# MINI_SAM_D51_016.net
KiCad netlist of a schematic drawn in EAGLE
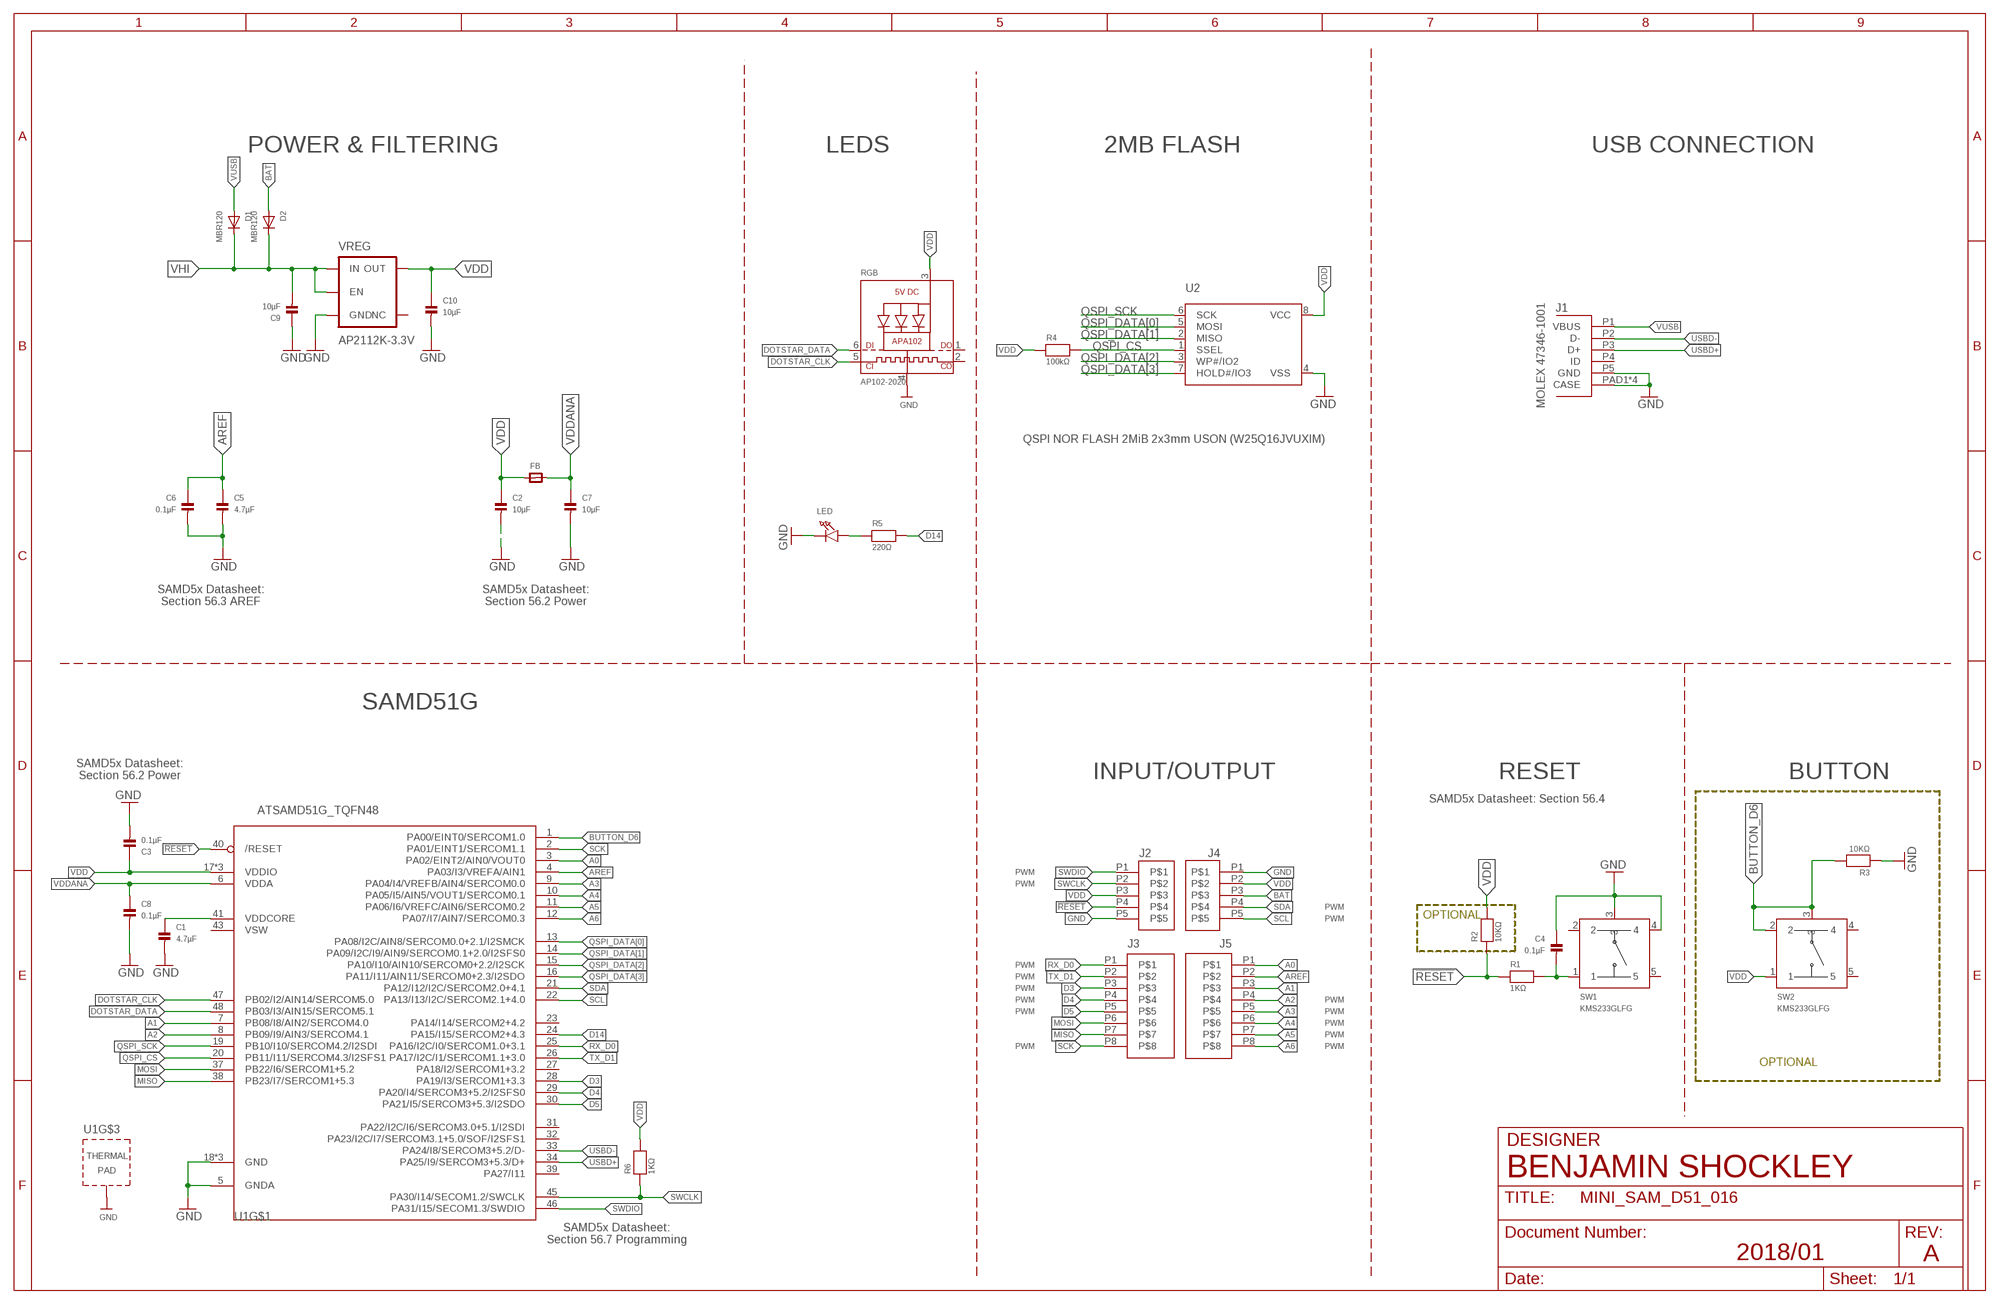
[diagram p0: schematic, sheet 1]

(export (version "E")
  (design (tool "Eeschema 10.0.6"))
  (components
    (comp (ref "C1")
      (value "4.7µF")
      (footprint "eagle-import:_0603MP")
      (libsource (lib "eagle-import") (part "CAP_CERAMIC_0603MP"))
    )
    (comp (ref "C2")
      (value "10µF")
      (footprint "eagle-import:_0603MP")
      (libsource (lib "eagle-import") (part "CAP_CERAMIC_0603MP"))
    )
    (comp (ref "C3")
      (value "0.1µF")
      (footprint "eagle-import:_0603MP")
      (libsource (lib "eagle-import") (part "CAP_CERAMIC_0603MP"))
    )
    (comp (ref "C4")
      (value "0.1µF")
      (footprint "eagle-import:_0603MP")
      (libsource (lib "eagle-import") (part "CAP_CERAMIC_0603MP"))
    )
    (comp (ref "C5")
      (value "4.7µF")
      (footprint "eagle-import:_0603MP")
      (libsource (lib "eagle-import") (part "CAP_CERAMIC_0603MP"))
    )
    (comp (ref "C6")
      (value "0.1µF")
      (footprint "eagle-import:_0603MP")
      (libsource (lib "eagle-import") (part "CAP_CERAMIC_0603MP"))
    )
    (comp (ref "C7")
      (value "10µF")
      (footprint "eagle-import:_0603MP")
      (libsource (lib "eagle-import") (part "CAP_CERAMIC_0603MP"))
    )
    (comp (ref "C8")
      (value "0.1µF")
      (footprint "eagle-import:_0603MP")
      (libsource (lib "eagle-import") (part "CAP_CERAMIC_0603MP"))
    )
    (comp (ref "C9")
      (value "10µF")
      (footprint "eagle-import:_0603MP")
      (libsource (lib "eagle-import") (part "CAP_CERAMIC_0603MP"))
    )
    (comp (ref "C10")
      (value "10µF")
      (footprint "eagle-import:_0603MP")
      (libsource (lib "eagle-import") (part "CAP_CERAMIC_0603MP"))
    )
    (comp (ref "D1")
      (value "MBR120")
      (footprint "eagle-import:SOD-123FL")
      (libsource (lib "eagle-import") (part "DIODE_SOD-123FL"))
    )
    (comp (ref "D2")
      (value "MBR120")
      (footprint "eagle-import:SOD-123FL")
      (libsource (lib "eagle-import") (part "DIODE_SOD-123FL"))
    )
    (comp (ref "FB")
      (value "Impedence: 50 ohm @ 20 MHz, 220 Ohm @ 100 MHz; low DC resistance")
      (footprint "eagle-import:_0603MP")
      (libsource (lib "eagle-import") (part "FERRITE_0603MP"))
    )
    (comp (ref "J1")
      (value "MOLEX_47346-100147346")
      (footprint "eagle-import:MOLEX_47346-1001")
      (libsource (lib "eagle-import") (part "MOLEX_47346-100147346"))
    )
    (comp (ref "J2")
      (value "1X5_HEADER_1.27MMCAST")
      (footprint "eagle-import:1X5_HEADER_1.27MM_CASTELLATED")
      (libsource (lib "eagle-import") (part "1X5_HEADER_1.27MMCAST"))
    )
    (comp (ref "J3")
      (value "1X8_HEADER_1.27MMCAST")
      (footprint "eagle-import:1X8_HEADER_1.27MM_CASTELLATED")
      (libsource (lib "eagle-import") (part "1X8_HEADER_1.27MMCAST"))
    )
    (comp (ref "J4")
      (value "1X5_HEADER_1.27MMCAST")
      (footprint "eagle-import:1X5_HEADER_1.27MM_CASTELLATED")
      (libsource (lib "eagle-import") (part "1X5_HEADER_1.27MMCAST"))
    )
    (comp (ref "J5")
      (value "1X8_HEADER_1.27MMCAST")
      (footprint "eagle-import:1X8_HEADER_1.27MM_CASTELLATED")
      (libsource (lib "eagle-import") (part "1X8_HEADER_1.27MMCAST"))
    )
    (comp (ref "LED")
      (value "Easily mounted up-sdie down.")
      (footprint "eagle-import:CHIPLED_0805_NOOUTLINE")
      (libsource (lib "eagle-import") (part "LED0805_NOOUTLINE"))
    )
    (comp (ref "R1")
      (value "1KΩ")
      (footprint "eagle-import:_0603MP")
      (libsource (lib "eagle-import") (part "RESISTOR_0603MP"))
    )
    (comp (ref "R2")
      (value "10KΩ")
      (footprint "eagle-import:_0603MP")
      (libsource (lib "eagle-import") (part "RESISTOR_0603MP"))
    )
    (comp (ref "R3")
      (value "10KΩ")
      (footprint "eagle-import:_0603MP")
      (libsource (lib "eagle-import") (part "RESISTOR_0603MP"))
    )
    (comp (ref "R4")
      (value "100kΩ")
      (footprint "eagle-import:_0603MP")
      (libsource (lib "eagle-import") (part "RESISTOR_0603MP"))
    )
    (comp (ref "R5")
      (value "220Ω")
      (footprint "eagle-import:_0603MP")
      (libsource (lib "eagle-import") (part "RESISTOR_0603MP"))
    )
    (comp (ref "R6")
      (value "1KΩ")
      (footprint "eagle-import:_0603MP")
      (libsource (lib "eagle-import") (part "RESISTOR_0603MP"))
    )
    (comp (ref "RGB")
      (value "AP102-2020")
      (footprint "eagle-import:APA102_2020")
      (libsource (lib "eagle-import") (part "APA1022020"))
    )
    (comp (ref "SW1")
      (value "KMS233GLFG")
      (footprint "eagle-import:KMS_SWITCH")
      (libsource (lib "eagle-import") (part "KMS_SWITCHKMS"))
    )
    (comp (ref "SW2")
      (value "KMS233GLFG")
      (footprint "eagle-import:KMS_SWITCH")
      (libsource (lib "eagle-import") (part "KMS_SWITCHKMS"))
    )
    (comp (ref "U1")
      (value "ATSAMD51G_TQFN48")
      (footprint "eagle-import:TQFN48_7MM")
      (libsource (lib "eagle-import") (part "ATSAMD51G_TQFN48"))
    )
    (comp (ref "U2")
      (value "QSPI NOR FLASH 2MiB 2x3mm USON (W25Q16JVUXIM)")
      (footprint "eagle-import:USON8")
      (libsource (lib "eagle-import") (part "SPIFLASH_8PINUX"))
    )
    (comp (ref "VREG")
      (value "AP2112K-3.3V")
      (footprint "eagle-import:SOT23-5")
      (libsource (lib "eagle-import") (part "V_REG_AP2112K-3.3V"))
    )
  )
  (nets
    (net (code "1") (name "/VSW") (class "Default")
      (node (ref "U1") (pin "43") (pinfunction "VSW_43") (pintype "power_in"))
    )
    (net (code "2") (name "/~{RESET}") (class "Default")
      (node (ref "J2") (pin "P4") (pinfunction "P$4_P4") (pintype "bidirectional"))
      (node (ref "R1") (pin "1") (pinfunction "1_1") (pintype "passive"))
      (node (ref "R2") (pin "1") (pinfunction "1_1") (pintype "passive"))
      (node (ref "U1") (pin "40") (pinfunction "/RESET_40") (pintype "bidirectional"))
    )
    (net (code "3") (name "A0") (class "Default")
      (node (ref "J5") (pin "P1") (pinfunction "P$1_P1") (pintype "bidirectional"))
      (node (ref "U1") (pin "3") (pinfunction "PA02/EINT2/AIN0/VOUT0_3") (pintype "bidirectional"))
    )
    (net (code "4") (name "A1") (class "Default")
      (node (ref "J5") (pin "P3") (pinfunction "P$3_P3") (pintype "bidirectional"))
      (node (ref "U1") (pin "7") (pinfunction "PB08/I8/AIN2/SERCOM4.0_7") (pintype "bidirectional"))
    )
    (net (code "5") (name "A2") (class "Default")
      (node (ref "J5") (pin "P4") (pinfunction "P$4_P4") (pintype "bidirectional"))
      (node (ref "U1") (pin "8") (pinfunction "PB09/I9/AIN3/SERCOM4.1_8") (pintype "bidirectional"))
    )
    (net (code "6") (name "A3") (class "Default")
      (node (ref "J5") (pin "P5") (pinfunction "P$5_P5") (pintype "bidirectional"))
      (node (ref "U1") (pin "9") (pinfunction "PA04/I4/VREFB/AIN4/SERCOM0.0_9") (pintype "bidirectional"))
    )
    (net (code "7") (name "A4") (class "Default")
      (node (ref "J5") (pin "P6") (pinfunction "P$6_P6") (pintype "bidirectional"))
      (node (ref "U1") (pin "10") (pinfunction "PA05/I5/AIN5/VOUT1/SERCOM0.1_10") (pintype "bidirectional"))
    )
    (net (code "8") (name "A5") (class "Default")
      (node (ref "J5") (pin "P7") (pinfunction "P$7_P7") (pintype "bidirectional"))
      (node (ref "U1") (pin "11") (pinfunction "PA06/I6/VREFC/AIN6/SERCOM0.2_11") (pintype "bidirectional"))
    )
    (net (code "9") (name "A6") (class "Default")
      (node (ref "J5") (pin "P8") (pinfunction "P$8_P8") (pintype "bidirectional"))
      (node (ref "U1") (pin "12") (pinfunction "PA07/I7/AIN7/SERCOM0.3_12") (pintype "bidirectional"))
    )
    (net (code "10") (name "AREF") (class "Default")
      (node (ref "C5") (pin "1") (pinfunction "P$1_1") (pintype "passive"))
      (node (ref "C6") (pin "1") (pinfunction "P$1_1") (pintype "passive"))
      (node (ref "J5") (pin "P2") (pinfunction "P$2_P2") (pintype "bidirectional"))
      (node (ref "U1") (pin "4") (pinfunction "PA03/I3/VREFA/AIN1_4") (pintype "bidirectional"))
    )
    (net (code "11") (name "BAT") (class "Default")
      (node (ref "D2") (pin "A") (pinfunction "A_A") (pintype "passive"))
      (node (ref "J4") (pin "P3") (pinfunction "P$3_P3") (pintype "bidirectional"))
    )
    (net (code "12") (name "BUTTON_D6") (class "Default")
      (node (ref "R3") (pin "2") (pinfunction "2_2") (pintype "passive"))
      (node (ref "SW2") (pin "2") (pinfunction "2_2") (pintype "bidirectional"))
      (node (ref "SW2") (pin "3") (pinfunction "3_3") (pintype "bidirectional"))
      (node (ref "U1") (pin "1") (pinfunction "PA00/EINT0/SERCOM1.0_1") (pintype "bidirectional"))
    )
    (net (code "13") (name "D3") (class "Default")
      (node (ref "J3") (pin "P3") (pinfunction "P$3_P3") (pintype "bidirectional"))
      (node (ref "U1") (pin "28") (pinfunction "PA19/I3/SERCOM1+3.3_28") (pintype "bidirectional"))
    )
    (net (code "14") (name "D4") (class "Default")
      (node (ref "J3") (pin "P4") (pinfunction "P$4_P4") (pintype "bidirectional"))
      (node (ref "U1") (pin "29") (pinfunction "PA20/I4/SERCOM3+5.2/I2SFS0_29") (pintype "bidirectional"))
    )
    (net (code "15") (name "D5") (class "Default")
      (node (ref "J3") (pin "P5") (pinfunction "P$5_P5") (pintype "bidirectional"))
      (node (ref "U1") (pin "30") (pinfunction "PA21/I5/SERCOM3+5.3/I2SDO_30") (pintype "bidirectional"))
    )
    (net (code "16") (name "D14") (class "Default")
      (node (ref "R5") (pin "2") (pinfunction "2_2") (pintype "passive"))
      (node (ref "U1") (pin "24") (pinfunction "PA15/I15/SERCOM2+4.3_24") (pintype "bidirectional"))
    )
    (net (code "17") (name "DOTSTAR_CLK") (class "Default")
      (node (ref "RGB") (pin "5") (pinfunction "CKI_5") (pintype "input"))
      (node (ref "U1") (pin "47") (pinfunction "PB02/I2/AIN14/SERCOM5.0_47") (pintype "bidirectional"))
    )
    (net (code "18") (name "DOTSTAR_DATA") (class "Default")
      (node (ref "RGB") (pin "6") (pinfunction "DI_6") (pintype "input"))
      (node (ref "U1") (pin "48") (pinfunction "PB03/I3/AIN15/SERCOM5.1_48") (pintype "bidirectional"))
    )
    (net (code "19") (name "GND") (class "Default")
      (node (ref "C1") (pin "2") (pinfunction "P$2_2") (pintype "passive"))
      (node (ref "C10") (pin "2") (pinfunction "P$2_2") (pintype "passive"))
      (node (ref "C2") (pin "2") (pinfunction "P$2_2") (pintype "passive"))
      (node (ref "C3") (pin "2") (pinfunction "P$2_2") (pintype "passive"))
      (node (ref "C4") (pin "1") (pinfunction "P$1_1") (pintype "passive"))
      (node (ref "C5") (pin "2") (pinfunction "P$2_2") (pintype "passive"))
      (node (ref "C6") (pin "2") (pinfunction "P$2_2") (pintype "passive"))
      (node (ref "C7") (pin "2") (pinfunction "P$2_2") (pintype "passive"))
      (node (ref "C8") (pin "2") (pinfunction "P$2_2") (pintype "passive"))
      (node (ref "C9") (pin "1") (pinfunction "P$1_1") (pintype "passive"))
      (node (ref "J1") (pin "P5") (pinfunction "GND_P5") (pintype "power_in"))
      (node (ref "J1") (pin "PAD1") (pinfunction "CASE_PAD1") (pintype "bidirectional"))
      (node (ref "J1") (pin "PAD2") (pinfunction "CASE_PAD2") (pintype "bidirectional"))
      (node (ref "J1") (pin "PAD3") (pinfunction "CASE_PAD3") (pintype "bidirectional"))
      (node (ref "J1") (pin "PAD4") (pinfunction "CASE_PAD4") (pintype "bidirectional"))
      (node (ref "J2") (pin "P5") (pinfunction "P$5_P5") (pintype "bidirectional"))
      (node (ref "J4") (pin "P1") (pinfunction "P$1_P1") (pintype "bidirectional"))
      (node (ref "LED") (pin "C") (pinfunction "C_C") (pintype "passive"))
      (node (ref "R3") (pin "1") (pinfunction "1_1") (pintype "passive"))
      (node (ref "RGB") (pin "4") (pinfunction "GND_4") (pintype "power_in"))
      (node (ref "SW1") (pin "3") (pinfunction "3_3") (pintype "bidirectional"))
      (node (ref "SW1") (pin "4") (pinfunction "4_4") (pintype "bidirectional"))
      (node (ref "U1") (pin "18") (pinfunction "GND_18") (pintype "power_in"))
      (node (ref "U1") (pin "35") (pinfunction "GND_35") (pintype "power_in"))
      (node (ref "U1") (pin "42") (pinfunction "GND_42") (pintype "power_in"))
      (node (ref "U1") (pin "5") (pinfunction "GNDA_5") (pintype "power_in"))
      (node (ref "U1") (pin "THERMAL") (pinfunction "TP_THERMAL") (pintype "power_in"))
      (node (ref "U2") (pin "4") (pinfunction "VSS_4") (pintype "bidirectional"))
      (node (ref "VREG") (pin "2") (pinfunction "GND_2") (pintype "input"))
    )
    (net (code "20") (name "MISO") (class "Default")
      (node (ref "J3") (pin "P7") (pinfunction "P$7_P7") (pintype "bidirectional"))
      (node (ref "U1") (pin "38") (pinfunction "PB23/I7/SERCOM1+5.3_38") (pintype "bidirectional"))
    )
    (net (code "21") (name "MOSI") (class "Default")
      (node (ref "J3") (pin "P6") (pinfunction "P$6_P6") (pintype "bidirectional"))
      (node (ref "U1") (pin "37") (pinfunction "PB22/I6/SERCOM1+5.2_37") (pintype "bidirectional"))
    )
    (net (code "22") (name "Net-(C1-P$1)") (class "Default")
      (node (ref "C1") (pin "1") (pinfunction "P$1_1") (pintype "passive"))
      (node (ref "U1") (pin "41") (pinfunction "VDDCORE_41") (pintype "power_in"))
    )
    (net (code "23") (name "Net-(C4-P$2)") (class "Default")
      (node (ref "C4") (pin "2") (pinfunction "P$2_2") (pintype "passive"))
      (node (ref "R1") (pin "2") (pinfunction "2_2") (pintype "passive"))
      (node (ref "SW1") (pin "1") (pinfunction "1_1") (pintype "bidirectional"))
    )
    (net (code "24") (name "Net-(LED-PadA)") (class "Default")
      (node (ref "LED") (pin "A") (pinfunction "A_A") (pintype "passive"))
      (node (ref "R5") (pin "1") (pinfunction "1_1") (pintype "passive"))
    )
    (net (code "25") (name "QSPI_CS") (class "Default")
      (node (ref "R4") (pin "2") (pinfunction "2_2") (pintype "passive"))
      (node (ref "U1") (pin "20") (pinfunction "PB11/I11/SERCOM4.3/I2SFS1_20") (pintype "bidirectional"))
      (node (ref "U2") (pin "1") (pinfunction "SSEL_1") (pintype "bidirectional"))
    )
    (net (code "26") (name "QSPI_DATA[0]") (class "Default")
      (node (ref "U1") (pin "13") (pinfunction "PA08/I2C/AIN8/SERCOM0.0+2.1/I2SMCK_13") (pintype "bidirectional"))
      (node (ref "U2") (pin "5") (pinfunction "MOSI_5") (pintype "bidirectional"))
    )
    (net (code "27") (name "QSPI_DATA[1]") (class "Default")
      (node (ref "U1") (pin "14") (pinfunction "PA09/I2C/I9/AIN9/SERCOM0.1+2.0/I2SFS0_14") (pintype "bidirectional"))
      (node (ref "U2") (pin "2") (pinfunction "MISO_2") (pintype "bidirectional"))
    )
    (net (code "28") (name "QSPI_DATA[2]") (class "Default")
      (node (ref "U1") (pin "15") (pinfunction "PA10/I10/AIN10/SERCOM0+2.2/I2SCK_15") (pintype "bidirectional"))
      (node (ref "U2") (pin "3") (pinfunction "WP#/IO2_3") (pintype "bidirectional"))
    )
    (net (code "29") (name "QSPI_DATA[3]") (class "Default")
      (node (ref "U1") (pin "16") (pinfunction "PA11/I11/AIN11/SERCOM0+2.3/I2SDO_16") (pintype "bidirectional"))
      (node (ref "U2") (pin "7") (pinfunction "HOLD#/IO3_7") (pintype "bidirectional"))
    )
    (net (code "30") (name "QSPI_SCK") (class "Default")
      (node (ref "U1") (pin "19") (pinfunction "PB10/I10/SERCOM4.2/I2SDI_19") (pintype "bidirectional"))
      (node (ref "U2") (pin "6") (pinfunction "SCK_6") (pintype "bidirectional"))
    )
    (net (code "31") (name "RX_D0") (class "Default")
      (node (ref "J3") (pin "P1") (pinfunction "P$1_P1") (pintype "bidirectional"))
      (node (ref "U1") (pin "25") (pinfunction "PA16/I2C/I0/SERCOM1.0+3.1_25") (pintype "bidirectional"))
    )
    (net (code "32") (name "SCK") (class "Default")
      (node (ref "J3") (pin "P8") (pinfunction "P$8_P8") (pintype "bidirectional"))
      (node (ref "U1") (pin "2") (pinfunction "PA01/EINT1/SERCOM1.1_2") (pintype "bidirectional"))
    )
    (net (code "33") (name "SCL") (class "Default")
      (node (ref "J4") (pin "P5") (pinfunction "P$5_P5") (pintype "bidirectional"))
      (node (ref "U1") (pin "22") (pinfunction "PA13/I13/I2C/SERCOM2.1+4.0_22") (pintype "bidirectional"))
    )
    (net (code "34") (name "SDA") (class "Default")
      (node (ref "J4") (pin "P4") (pinfunction "P$4_P4") (pintype "bidirectional"))
      (node (ref "U1") (pin "21") (pinfunction "PA12/I12/I2C/SERCOM2.0+4.1_21") (pintype "bidirectional"))
    )
    (net (code "35") (name "SWCLK") (class "Default")
      (node (ref "J2") (pin "P2") (pinfunction "P$2_P2") (pintype "bidirectional"))
      (node (ref "R6") (pin "1") (pinfunction "1_1") (pintype "passive"))
      (node (ref "U1") (pin "45") (pinfunction "PA30/I14/SECOM1.2/SWCLK_45") (pintype "bidirectional"))
    )
    (net (code "36") (name "SWDIO") (class "Default")
      (node (ref "J2") (pin "P1") (pinfunction "P$1_P1") (pintype "bidirectional"))
      (node (ref "U1") (pin "46") (pinfunction "PA31/I15/SECOM1.3/SWDIO_46") (pintype "bidirectional"))
    )
    (net (code "37") (name "TX_D1") (class "Default")
      (node (ref "J3") (pin "P2") (pinfunction "P$2_P2") (pintype "bidirectional"))
      (node (ref "U1") (pin "26") (pinfunction "PA17/I2C/I1/SERCOM1.1+3.0_26") (pintype "bidirectional"))
    )
    (net (code "38") (name "USBD+") (class "Default")
      (node (ref "J1") (pin "P3") (pinfunction "D+_P3") (pintype "bidirectional"))
      (node (ref "U1") (pin "34") (pinfunction "PA25/I9/SERCOM3+5.3/D+_34") (pintype "bidirectional"))
    )
    (net (code "39") (name "USBD-") (class "Default")
      (node (ref "J1") (pin "P2") (pinfunction "D-_P2") (pintype "bidirectional"))
      (node (ref "U1") (pin "33") (pinfunction "PA24/I8/SERCOM3+5.2/D-_33") (pintype "bidirectional"))
    )
    (net (code "40") (name "VDD") (class "Default")
      (node (ref "C10") (pin "1") (pinfunction "P$1_1") (pintype "passive"))
      (node (ref "C2") (pin "1") (pinfunction "P$1_1") (pintype "passive"))
      (node (ref "C3") (pin "1") (pinfunction "P$1_1") (pintype "passive"))
      (node (ref "FB") (pin "1") (pinfunction "P$1_1") (pintype "passive"))
      (node (ref "J2") (pin "P3") (pinfunction "P$3_P3") (pintype "bidirectional"))
      (node (ref "J4") (pin "P2") (pinfunction "P$2_P2") (pintype "bidirectional"))
      (node (ref "R2") (pin "2") (pinfunction "2_2") (pintype "passive"))
      (node (ref "R4") (pin "1") (pinfunction "1_1") (pintype "passive"))
      (node (ref "R6") (pin "2") (pinfunction "2_2") (pintype "passive"))
      (node (ref "RGB") (pin "3") (pinfunction "VDD_3") (pintype "power_in"))
      (node (ref "SW2") (pin "1") (pinfunction "1_1") (pintype "bidirectional"))
      (node (ref "U1") (pin "17") (pinfunction "VDDIO_17") (pintype "power_in"))
      (node (ref "U1") (pin "36") (pinfunction "VDDIO_36") (pintype "power_in"))
      (node (ref "U1") (pin "44") (pinfunction "VDDIO_44") (pintype "power_in"))
      (node (ref "U2") (pin "8") (pinfunction "VCC_8") (pintype "bidirectional"))
      (node (ref "VREG") (pin "5") (pinfunction "OUT_5") (pintype "passive"))
    )
    (net (code "41") (name "VDDANA") (class "Default")
      (node (ref "C7") (pin "1") (pinfunction "P$1_1") (pintype "passive"))
      (node (ref "C8") (pin "1") (pinfunction "P$1_1") (pintype "passive"))
      (node (ref "FB") (pin "2") (pinfunction "P$2_2") (pintype "passive"))
      (node (ref "U1") (pin "6") (pinfunction "VDDA_6") (pintype "power_in"))
    )
    (net (code "42") (name "VHI") (class "Default")
      (node (ref "C9") (pin "2") (pinfunction "P$2_2") (pintype "passive"))
      (node (ref "D1") (pin "C") (pinfunction "C_C") (pintype "passive"))
      (node (ref "D2") (pin "C") (pinfunction "C_C") (pintype "passive"))
      (node (ref "VREG") (pin "1") (pinfunction "IN_1") (pintype "input"))
      (node (ref "VREG") (pin "3") (pinfunction "EN_3") (pintype "input"))
    )
    (net (code "43") (name "VUSB") (class "Default")
      (node (ref "D1") (pin "A") (pinfunction "A_A") (pintype "passive"))
      (node (ref "J1") (pin "P1") (pinfunction "VBUS_P1") (pintype "power_in"))
    )
    (net (code "44") (name "unconnected-(J1-ID-PadP4)") (class "Default")
      (node (ref "J1") (pin "P4") (pinfunction "ID_P4") (pintype "bidirectional"))
    )
    (net (code "45") (name "unconnected-(RGB-CKO-Pad2)") (class "Default")
      (node (ref "RGB") (pin "2") (pinfunction "CKO_2") (pintype "output"))
    )
    (net (code "46") (name "unconnected-(RGB-DO-Pad1)") (class "Default")
      (node (ref "RGB") (pin "1") (pinfunction "DO_1") (pintype "output"))
    )
    (net (code "47") (name "unconnected-(SW1-Pad2)") (class "Default")
      (node (ref "SW1") (pin "2") (pinfunction "2_2") (pintype "bidirectional"))
    )
    (net (code "48") (name "unconnected-(SW1-Pad5)") (class "Default")
      (node (ref "SW1") (pin "5") (pinfunction "5_5") (pintype "bidirectional"))
    )
    (net (code "49") (name "unconnected-(SW2-Pad4)") (class "Default")
      (node (ref "SW2") (pin "4") (pinfunction "4_4") (pintype "bidirectional"))
    )
    (net (code "50") (name "unconnected-(SW2-Pad5)") (class "Default")
      (node (ref "SW2") (pin "5") (pinfunction "5_5") (pintype "bidirectional"))
    )
    (net (code "51") (name "unconnected-(U1A-PA14{slash}I14{slash}SERCOM2+4.2-Pad23)") (class "Default")
      (node (ref "U1") (pin "23") (pinfunction "PA14/I14/SERCOM2+4.2_23") (pintype "bidirectional"))
    )
    (net (code "52") (name "unconnected-(U1A-PA18{slash}I2{slash}SERCOM1+3.2-Pad27)") (class "Default")
      (node (ref "U1") (pin "27") (pinfunction "PA18/I2/SERCOM1+3.2_27") (pintype "bidirectional"))
    )
    (net (code "53") (name "unconnected-(U1A-PA22{slash}I2C{slash}I6{slash}SERCOM3.0+5.1{slash}I2SDI-Pad31)") (class "Default")
      (node (ref "U1") (pin "31") (pinfunction "PA22/I2C/I6/SERCOM3.0+5.1/I2SDI_31") (pintype "bidirectional"))
    )
    (net (code "54") (name "unconnected-(U1A-PA23{slash}I2C{slash}I7{slash}SERCOM3.1+5.0{slash}SOF{slash}I2SFS1-Pad32)") (class "Default")
      (node (ref "U1") (pin "32") (pinfunction "PA23/I2C/I7/SERCOM3.1+5.0/SOF/I2SFS1_32") (pintype "bidirectional"))
    )
    (net (code "55") (name "unconnected-(U1A-PA27{slash}I11-Pad39)") (class "Default")
      (node (ref "U1") (pin "39") (pinfunction "PA27/I11_39") (pintype "bidirectional"))
    )
    (net (code "56") (name "unconnected-(VREG-NC-Pad4)") (class "Default")
      (node (ref "VREG") (pin "4") (pinfunction "NC_4") (pintype "input"))
    )
  )
)
